# PWR_Board.net
KiCad netlist of a schematic drawn in Altium Designer
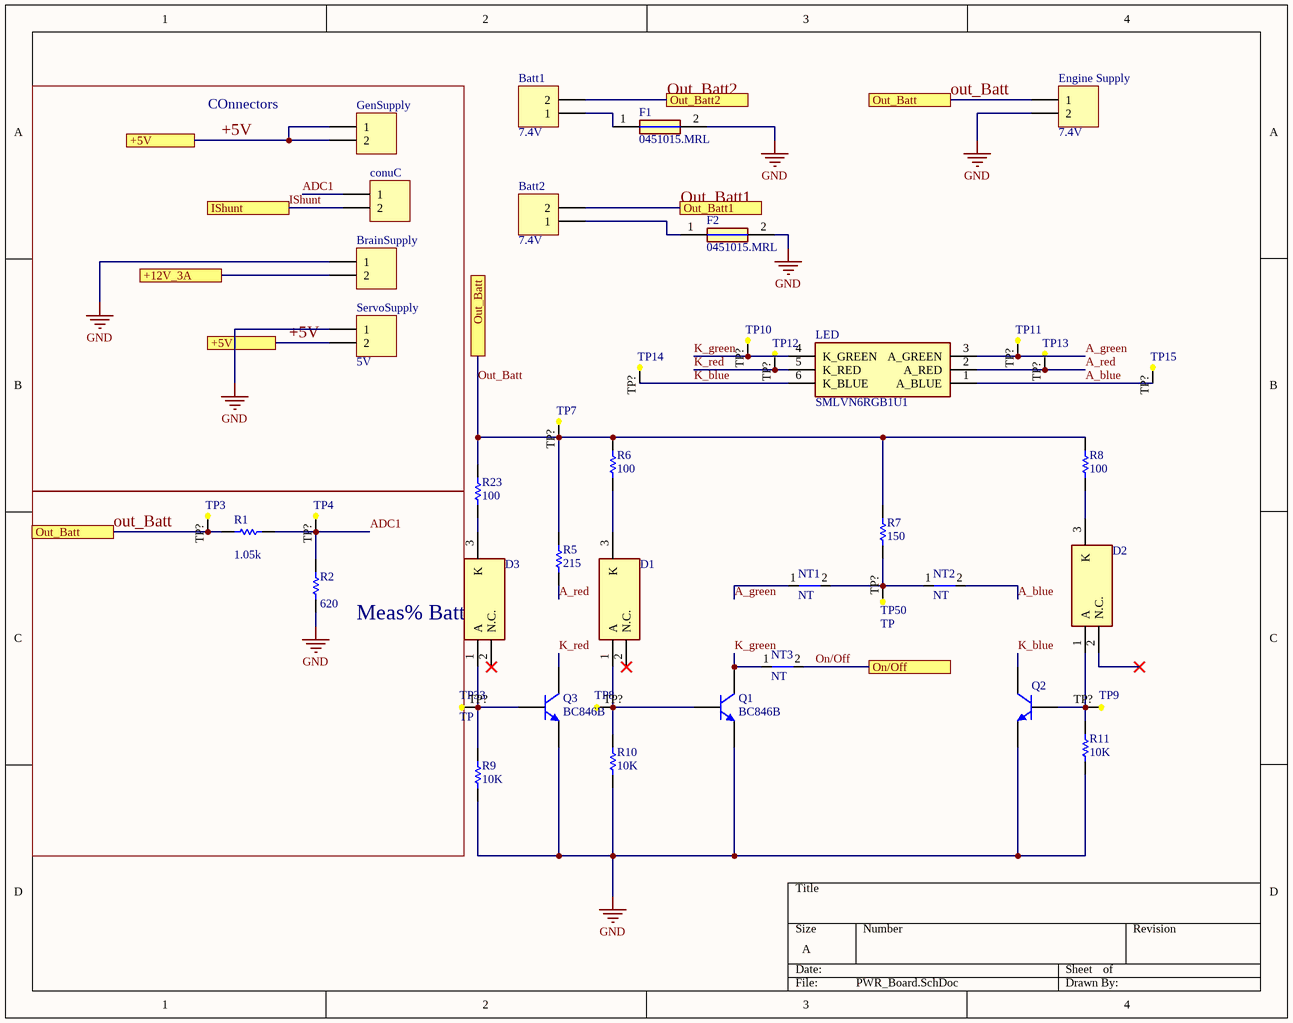
[diagram p0: PWR_Board.SchDoc]

(export (version "E")
  (design (tool "Eeschema 10.0.6"))
  (components
    (comp (ref "Batt1")
      (value "7.4V")
      (footprint "PCBComponent_1 - duplicate")
      (description "2 Holes")
      (fields (field (name "PUBLISHER") "Altium Limited"))
      (libsource (lib "Miscellaneous Connectors") (part "Header 2"))
    )
    (comp (ref "Batt2")
      (value "7.4V")
      (footprint "PCBComponent_1 - duplicate")
      (description "2 Holes")
      (fields (field (name "PUBLISHER") "Altium Limited"))
      (libsource (lib "Miscellaneous Connectors") (part "Header 2"))
    )
    (comp (ref "BrainSupply")
      (value "6.1V-7.4V")
      (footprint "TB002V50002BE")
      (description "Header, 2-Pin")
      (fields (field (name "PUBLISHER") "Altium Limited"))
      (libsource (lib "") (part "Header 2_1"))
    )
    (comp (ref "conuC")
      (value "6.1V-7.4V")
      (footprint "TB002V50002BE")
      (description "Header, 2-Pin")
      (fields (field (name "PUBLISHER") "Altium Limited"))
      (libsource (lib "") (part "Header 2_1"))
    )
    (comp (ref "D1")
      (value "Vbr=6V2")
      (footprint "SOT65P210X110-3N")
      (description "Zener Diode")
      (fields
        (field (name "MANUFACTURER_PART_NUMBER") "BZX84W-C15F")
        (field (name "MOUSER PART NUMBER") "771-BZX84W-C15F")
      )
      (libsource (lib "BZX84(sot 23)") (part "BZX84W-C15F"))
    )
    (comp (ref "D2")
      (value "BZX84W-C15F")
      (footprint "SOT95P230X110-3N")
      (description "Zener Diode")
      (fields (field (name "MOUSER PART NUMBER") "771-BZX84W-C15F"))
      (libsource (lib "BZX84(sot 23)") (part "BZX84W-C15F"))
    )
    (comp (ref "D3")
      (value "Vbr=6V2")
      (footprint "SOT95P230X110-3N")
      (description "Zener Diode")
      (fields
        (field (name "MANUFACTURER_PART_NUMBER") "BZX84W-C15F")
        (field (name "MOUSER PART NUMBER") "771-BZX84W-C15F")
      )
      (libsource (lib "BZX84(sot 23)") (part "BZX84W-C15F"))
    )
    (comp (ref "Engine Supply")
      (value "7.4V")
      (footprint "PCBComponent_1 - duplicate")
      (description "2 Holes")
      (fields (field (name "PUBLISHER") "Altium Limited"))
      (libsource (lib "") (part "Header 2_1"))
    )
    (comp (ref "F1")
      (value "0451015.MRL")
      (footprint "SamacSys:FUSC6127X294N")
      (description "Fuse")
      (fields (field (name "MOUSER PART NUMBER") "576-0451015.MRL"))
      (libsource (lib "0451015.MRL(6.1x2.69)") (part "0451015.MRL"))
    )
    (comp (ref "F2")
      (value "0451015.MRL")
      (footprint "SamacSys:FUSC6127X294N")
      (description "Fuse")
      (fields (field (name "MOUSER PART NUMBER") "576-0451015.MRL"))
      (libsource (lib "0451015.MRL(6.1x2.69)") (part "0451015.MRL"))
    )
    (comp (ref "GenSupply")
      (value "6.1V-7.4V")
      (footprint "TB002V50002BE")
      (description "Header, 2-Pin")
      (fields (field (name "PUBLISHER") "Altium Limited"))
      (libsource (lib "") (part "Header 2_1"))
    )
    (comp (ref "LED")
      (value "SMLVN6RGB1U1")
      (footprint "SMLVN6RGB1U1")
      (description "LED")
      (fields (field (name "MOUSER PART NUMBER") "755-SMLVN6RGB1U1"))
      (libsource (lib "SMLVN6RGB1W1 ") (part "SMLVN6RGB1U1"))
    )
    (comp (ref "NT1")
      (value "NT")
      (footprint "NetTie")
      (description "Net Tie SMD")
      (libsource (lib "NetTie") (part "NetTie"))
    )
    (comp (ref "NT2")
      (value "NT")
      (footprint "NetTie")
      (description "Net Tie SMD")
      (libsource (lib "NetTie") (part "NetTie"))
    )
    (comp (ref "NT3")
      (value "NT")
      (footprint "NetTie")
      (description "Net Tie SMD")
      (libsource (lib "NetTie") (part "NetTie"))
    )
    (comp (ref "Q1")
      (value "BC846B")
      (footprint "SOT95P230X110-3N")
      (description "NPN Bipolar Transistor")
      (fields (field (name "PUBLISHER") "Altium Limited"))
      (libsource (lib "Miscellaneous Devices") (part "NPN"))
    )
    (comp (ref "Q2")
      (value "BC846B")
      (footprint "SOT95P230X110-3N")
      (description "NPN Bipolar Transistor")
      (fields (field (name "PUBLISHER") "Altium Limited"))
      (libsource (lib "Miscellaneous Devices") (part "NPN"))
    )
    (comp (ref "Q3")
      (value "BC846B")
      (footprint "SOT95P230X110-3N")
      (description "NPN Bipolar Transistor")
      (fields (field (name "PUBLISHER") "Altium Limited"))
      (libsource (lib "Miscellaneous Devices") (part "NPN"))
    )
    (comp (ref "R1")
      (value "1.05k")
      (footprint "RESC1608X55N")
      (description "Resistor")
      (fields (field (name "Comment") "MCR03..PFX1051") (field (name "PUBLISHER") "Altium Limited"))
      (libsource (lib "Miscellaneous Devices") (part "Res1"))
    )
    (comp (ref "R2")
      (value "620")
      (footprint "RESC1608X55N")
      (description "Resistor")
      (fields (field (name "Comment") "MCR03...PFX7680") (field (name "PUBLISHER") "Altium Limited"))
      (libsource (lib "Miscellaneous Devices") (part "Res1"))
    )
    (comp (ref "R5")
      (value "RK73H1JPT..2150F")
      (footprint "ERJ2RKD1004X")
      (description "Resistor")
      (fields (field (name "ERJ2RKF2150..") "215") (field (name "PUBLISHER") "Altium Limited"))
      (libsource (lib "Miscellaneous Devices") (part "Res1"))
    )
    (comp (ref "R6")
      (value "100")
      (footprint "RESC1608X55N")
      (description "Resistor")
      (fields (field (name "Comment") "MCR03..PFX1000") (field (name "PUBLISHER") "Altium Limited"))
      (libsource (lib "Miscellaneous Devices") (part "Res1"))
    )
    (comp (ref "R7")
      (value "150")
      (footprint "SMM02040D1501BB300")
      (description "Resistor")
      (fields (field (name "Comment") "SMM0204 50 150R 1 %") (field (name "PUBLISHER") "Altium Limited"))
      (libsource (lib "Miscellaneous Devices") (part "Res1"))
    )
    (comp (ref "R8")
      (value "100")
      (footprint "RESC1608X55N")
      (description "Resistor")
      (fields (field (name "Comment") "MCR03..PFX1000") (field (name "PUBLISHER") "Altium Limited"))
      (libsource (lib "Miscellaneous Devices") (part "Res1"))
    )
    (comp (ref "R9")
      (value "10K")
      (footprint "RESC1608X55N")
      (description "Resistor")
      (fields (field (name "Comment") "MCR03..PFX1002") (field (name "PUBLISHER") "Altium Limited"))
      (libsource (lib "Miscellaneous Devices") (part "Res1"))
    )
    (comp (ref "R10")
      (value "10K")
      (footprint "RESC1608X55N")
      (description "Resistor")
      (fields (field (name "Comment") "MCR03..PFX1002") (field (name "PUBLISHER") "Altium Limited"))
      (libsource (lib "Miscellaneous Devices") (part "Res1"))
    )
    (comp (ref "R11")
      (value "10K")
      (footprint "RESC1608X55N")
      (description "Resistor")
      (fields (field (name "Comment") "MCR03..PFX1002") (field (name "PUBLISHER") "Altium Limited"))
      (libsource (lib "Miscellaneous Devices") (part "Res1"))
    )
    (comp (ref "R23")
      (value "100")
      (footprint "RESC1608X55N")
      (description "Resistor")
      (fields (field (name "Comment") "MCR03..PFX1000") (field (name "PUBLISHER") "Altium Limited"))
      (libsource (lib "Miscellaneous Devices") (part "Res1"))
    )
    (comp (ref "ServoSupply")
      (value "5V")
      (footprint "TB002V50002BE")
      (description "Header, 2-Pin")
      (fields (field (name "PUBLISHER") "Altium Limited"))
      (libsource (lib "") (part "Header 2_1"))
    )
    (comp (ref "TP3")
      (value "TP")
      (footprint "Test_Point0.5x0.5")
      (libsource (lib "TP_0.6x0.6") (part "TEst_Point_0.5x0.5"))
    )
    (comp (ref "TP4")
      (value "TP")
      (footprint "Test_Point0.5x0.5")
      (libsource (lib "TP_0.6x0.6") (part "TEst_Point_0.5x0.5"))
    )
    (comp (ref "TP7")
      (value "TP")
      (footprint "Test_Point0.5x0.5")
      (libsource (lib "TP_0.6x0.6") (part "TEst_Point_0.5x0.5"))
    )
    (comp (ref "TP8")
      (value "TP")
      (footprint "Test_Point0.5x0.5")
      (libsource (lib "TP_0.6x0.6") (part "TEst_Point_0.5x0.5"))
    )
    (comp (ref "TP9")
      (value "TP")
      (footprint "Test_Point0.5x0.5")
      (libsource (lib "TP_0.6x0.6") (part "TEst_Point_0.5x0.5"))
    )
    (comp (ref "TP10")
      (value "TP")
      (footprint "Test_Point0.5x0.5")
      (libsource (lib "TP_0.6x0.6") (part "TEst_Point_0.5x0.5"))
    )
    (comp (ref "TP11")
      (value "TP")
      (footprint "Test_Point0.5x0.5")
      (libsource (lib "TP_0.6x0.6") (part "TEst_Point_0.5x0.5"))
    )
    (comp (ref "TP12")
      (value "TP")
      (footprint "Test_Point0.5x0.5")
      (libsource (lib "TP_0.6x0.6") (part "TEst_Point_0.5x0.5"))
    )
    (comp (ref "TP13")
      (value "TP")
      (footprint "Test_Point0.5x0.5")
      (libsource (lib "TP_0.6x0.6") (part "TEst_Point_0.5x0.5"))
    )
    (comp (ref "TP14")
      (value "TP")
      (footprint "Test_Point0.5x0.5")
      (libsource (lib "TP_0.6x0.6") (part "TEst_Point_0.5x0.5"))
    )
    (comp (ref "TP15")
      (value "TP")
      (footprint "Test_Point0.5x0.5")
      (libsource (lib "TP_0.6x0.6") (part "TEst_Point_0.5x0.5"))
    )
    (comp (ref "TP33")
      (value "TP")
      (footprint "Test_Point0.5x0.5")
      (libsource (lib "TP_0.6x0.6") (part "TEst_Point_0.5x0.5"))
    )
    (comp (ref "TP50")
      (value "TP")
      (footprint "Test_Point0.5x0.5")
      (libsource (lib "TP_0.6x0.6") (part "TEst_Point_0.5x0.5"))
    )
  )
  (nets
    (net (code "1") (name "/+5V") (class "Default")
      (node (ref "GenSupply") (pin "1") (pinfunction "1_1") (pintype "passive"))
      (node (ref "GenSupply") (pin "2") (pinfunction "2_2") (pintype "passive"))
      (node (ref "ServoSupply") (pin "2") (pinfunction "2_2") (pintype "passive"))
    )
    (net (code "2") (name "/+12V_3A") (class "Default")
      (node (ref "BrainSupply") (pin "2") (pinfunction "2_2") (pintype "passive"))
    )
    (net (code "3") (name "/ADC1") (class "Default")
      (node (ref "R1") (pin "1") (pinfunction "1_1") (pintype "passive"))
      (node (ref "R2") (pin "1") (pinfunction "1_1") (pintype "passive"))
      (node (ref "TP4") (pin "TP?") (pinfunction "TP_TP?") (pintype "passive"))
      (node (ref "conuC") (pin "1") (pinfunction "1_1") (pintype "passive"))
    )
    (net (code "4") (name "/A_blue") (class "Default")
      (node (ref "LED") (pin "1") (pinfunction "A_BLUE_1") (pintype "passive"))
      (node (ref "NT2") (pin "2") (pinfunction "2_2") (pintype "passive"))
      (node (ref "TP15") (pin "TP?") (pinfunction "TP_TP?") (pintype "passive"))
    )
    (net (code "5") (name "/A_green") (class "Default")
      (node (ref "LED") (pin "3") (pinfunction "A_GREEN_3") (pintype "passive"))
      (node (ref "NT1") (pin "1") (pinfunction "1_1") (pintype "passive"))
      (node (ref "TP11") (pin "TP?") (pinfunction "TP_TP?") (pintype "passive"))
    )
    (net (code "6") (name "/A_red") (class "Default")
      (node (ref "LED") (pin "2") (pinfunction "A_RED_2") (pintype "passive"))
      (node (ref "R5") (pin "2") (pinfunction "2_2") (pintype "passive"))
      (node (ref "TP13") (pin "TP?") (pinfunction "TP_TP?") (pintype "passive"))
    )
    (net (code "7") (name "/IShunt") (class "Default")
      (node (ref "conuC") (pin "2") (pinfunction "2_2") (pintype "passive"))
    )
    (net (code "8") (name "/K_blue") (class "Default")
      (node (ref "LED") (pin "6") (pinfunction "K_BLUE_6") (pintype "passive"))
      (node (ref "Q2") (pin "3") (pinfunction "C_3") (pintype "passive"))
      (node (ref "TP14") (pin "TP?") (pinfunction "TP_TP?") (pintype "passive"))
    )
    (net (code "9") (name "/K_green") (class "Default")
      (node (ref "LED") (pin "4") (pinfunction "K_GREEN_4") (pintype "passive"))
      (node (ref "NT3") (pin "1") (pinfunction "1_1") (pintype "passive"))
      (node (ref "Q1") (pin "3") (pinfunction "C_3") (pintype "passive"))
      (node (ref "TP10") (pin "TP?") (pinfunction "TP_TP?") (pintype "passive"))
    )
    (net (code "10") (name "/K_red") (class "Default")
      (node (ref "LED") (pin "5") (pinfunction "K_RED_5") (pintype "passive"))
      (node (ref "Q3") (pin "3") (pinfunction "C_3") (pintype "passive"))
      (node (ref "TP12") (pin "TP?") (pinfunction "TP_TP?") (pintype "passive"))
    )
    (net (code "11") (name "/On{slash}Off") (class "Default")
      (node (ref "NT3") (pin "2") (pinfunction "2_2") (pintype "passive"))
    )
    (net (code "12") (name "/Out_Batt") (class "Default")
      (node (ref "Engine Supply") (pin "1") (pinfunction "1_1") (pintype "passive"))
      (node (ref "R1") (pin "2") (pinfunction "2_2") (pintype "passive"))
      (node (ref "R23") (pin "1") (pinfunction "1_1") (pintype "passive"))
      (node (ref "R5") (pin "1") (pinfunction "1_1") (pintype "passive"))
      (node (ref "R6") (pin "1") (pinfunction "1_1") (pintype "passive"))
      (node (ref "R7") (pin "1") (pinfunction "1_1") (pintype "passive"))
      (node (ref "R8") (pin "1") (pinfunction "1_1") (pintype "passive"))
      (node (ref "TP3") (pin "TP?") (pinfunction "TP_TP?") (pintype "passive"))
      (node (ref "TP7") (pin "TP?") (pinfunction "TP_TP?") (pintype "passive"))
    )
    (net (code "13") (name "/Out_Batt1") (class "Default")
      (node (ref "Batt2") (pin "2") (pinfunction "2_2") (pintype "passive"))
    )
    (net (code "14") (name "/Out_Batt2") (class "Default")
      (node (ref "Batt1") (pin "2") (pinfunction "2_2") (pintype "passive"))
    )
    (net (code "15") (name "GND") (class "Default")
      (node (ref "BrainSupply") (pin "1") (pinfunction "1_1") (pintype "passive"))
      (node (ref "Engine Supply") (pin "2") (pinfunction "2_2") (pintype "passive"))
      (node (ref "F1") (pin "2") (pinfunction "2_2") (pintype "passive"))
      (node (ref "F2") (pin "2") (pinfunction "2_2") (pintype "passive"))
      (node (ref "Q1") (pin "2") (pinfunction "E_2") (pintype "passive"))
      (node (ref "Q2") (pin "2") (pinfunction "E_2") (pintype "passive"))
      (node (ref "Q3") (pin "2") (pinfunction "E_2") (pintype "passive"))
      (node (ref "R10") (pin "2") (pinfunction "2_2") (pintype "passive"))
      (node (ref "R11") (pin "2") (pinfunction "2_2") (pintype "passive"))
      (node (ref "R2") (pin "2") (pinfunction "2_2") (pintype "passive"))
      (node (ref "R9") (pin "2") (pinfunction "2_2") (pintype "passive"))
      (node (ref "ServoSupply") (pin "1") (pinfunction "1_1") (pintype "passive"))
    )
    (net (code "16") (name "Net-(Batt1-Pad1)") (class "Default")
      (node (ref "Batt1") (pin "1") (pinfunction "1_1") (pintype "passive"))
      (node (ref "F1") (pin "1") (pinfunction "1_1") (pintype "passive"))
    )
    (net (code "17") (name "Net-(Batt2-Pad1)") (class "Default")
      (node (ref "Batt2") (pin "1") (pinfunction "1_1") (pintype "passive"))
      (node (ref "F2") (pin "1") (pinfunction "1_1") (pintype "passive"))
    )
    (net (code "18") (name "Net-(D1-A)") (class "Default")
      (node (ref "D1") (pin "1") (pinfunction "A_1") (pintype "passive"))
      (node (ref "Q1") (pin "1") (pinfunction "B_1") (pintype "passive"))
      (node (ref "R10") (pin "1") (pinfunction "1_1") (pintype "passive"))
      (node (ref "TP8") (pin "TP?") (pinfunction "TP_TP?") (pintype "passive"))
    )
    (net (code "19") (name "Net-(D1-K)") (class "Default")
      (node (ref "D1") (pin "3") (pinfunction "K_3") (pintype "passive"))
      (node (ref "R6") (pin "2") (pinfunction "2_2") (pintype "passive"))
    )
    (net (code "20") (name "Net-(D2-A)") (class "Default")
      (node (ref "D2") (pin "1") (pinfunction "A_1") (pintype "passive"))
      (node (ref "Q2") (pin "1") (pinfunction "B_1") (pintype "passive"))
      (node (ref "R11") (pin "1") (pinfunction "1_1") (pintype "passive"))
      (node (ref "TP9") (pin "TP?") (pinfunction "TP_TP?") (pintype "passive"))
    )
    (net (code "21") (name "Net-(D2-K)") (class "Default")
      (node (ref "D2") (pin "3") (pinfunction "K_3") (pintype "passive"))
      (node (ref "R8") (pin "2") (pinfunction "2_2") (pintype "passive"))
    )
    (net (code "22") (name "Net-(D3-A)") (class "Default")
      (node (ref "D3") (pin "1") (pinfunction "A_1") (pintype "passive"))
      (node (ref "Q3") (pin "1") (pinfunction "B_1") (pintype "passive"))
      (node (ref "R9") (pin "1") (pinfunction "1_1") (pintype "passive"))
      (node (ref "TP33") (pin "TP?") (pinfunction "TP_TP?") (pintype "passive"))
    )
    (net (code "23") (name "Net-(D3-K)") (class "Default")
      (node (ref "D3") (pin "3") (pinfunction "K_3") (pintype "passive"))
      (node (ref "R23") (pin "2") (pinfunction "2_2") (pintype "passive"))
    )
    (net (code "24") (name "Net-(TP50-TP)") (class "Default")
      (node (ref "NT1") (pin "2") (pinfunction "2_2") (pintype "passive"))
      (node (ref "NT2") (pin "1") (pinfunction "1_1") (pintype "passive"))
      (node (ref "R7") (pin "2") (pinfunction "2_2") (pintype "passive"))
      (node (ref "TP50") (pin "TP?") (pinfunction "TP_TP?") (pintype "passive"))
    )
    (net (code "25") (name "unconnected-(D1-N.C.-Pad2)") (class "Default")
      (node (ref "D1") (pin "2") (pinfunction "N.C._2") (pintype "passive+no_connect"))
    )
    (net (code "26") (name "unconnected-(D2-N.C.-Pad2)") (class "Default")
      (node (ref "D2") (pin "2") (pinfunction "N.C._2") (pintype "passive+no_connect"))
    )
    (net (code "27") (name "unconnected-(D3-N.C.-Pad2)") (class "Default")
      (node (ref "D3") (pin "2") (pinfunction "N.C._2") (pintype "passive+no_connect"))
    )
  )
)
